# Jerry_microMouse.net
KiCad netlist of a schematic drawn in EAGLE
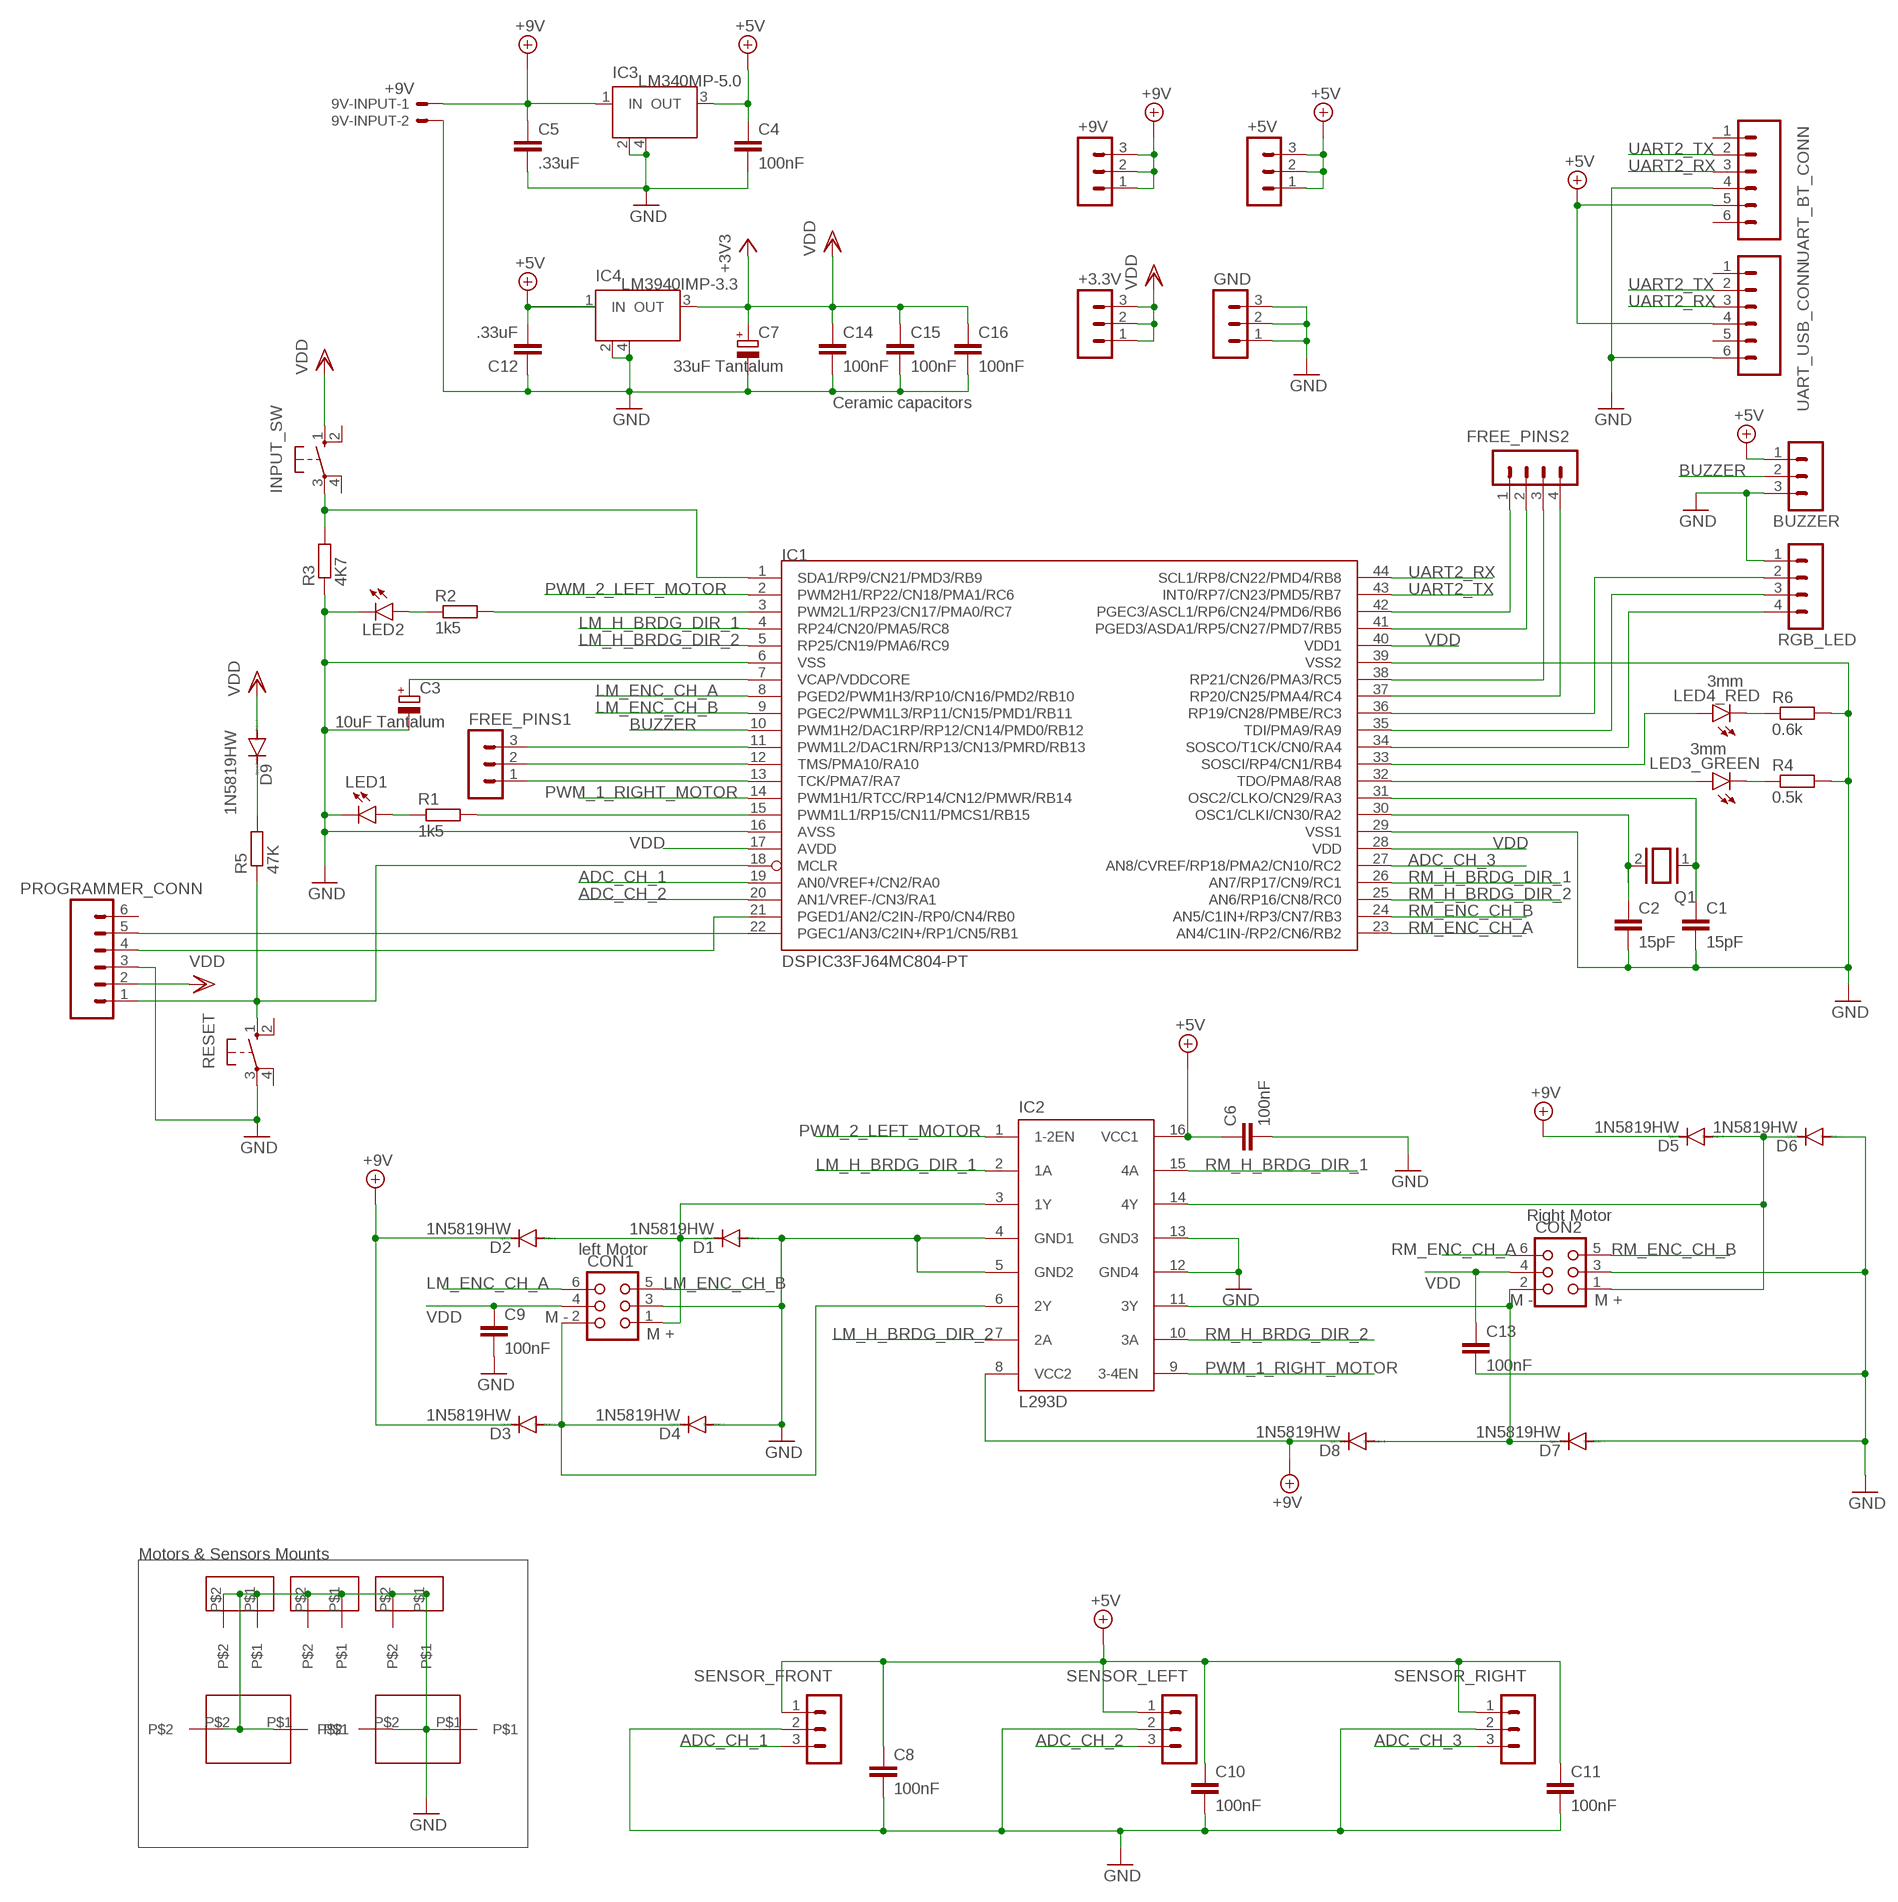
[diagram p0: schematic, sheet 1]

(export (version "E")
  (design (tool "Eeschema 10.0.6"))
  (components
    (comp (ref "+3.3V")
      (value "MA03-1")
      (footprint "eagle-import:MA03-1")
      (libsource (lib "eagle-import") (part "MA03-1"))
    )
    (comp (ref "+5V")
      (value "MA03-1")
      (footprint "eagle-import:MA03-1")
      (libsource (lib "eagle-import") (part "MA03-1"))
    )
    (comp (ref "+9V")
      (value "MA03-1")
      (footprint "eagle-import:MA03-1")
      (libsource (lib "eagle-import") (part "MA03-1"))
    )
    (comp (ref "9V-INPUT")
      (value "+9V")
      (footprint "eagle-import:22-23-2021")
      (fields (field (name "MF") "MOLEX") (field (name "MPN") "22-23-2021"))
      (libsource (lib "eagle-import") (part "22-23-2021"))
    )
    (comp (ref "BUZZER")
      (value "MA03-1")
      (footprint "eagle-import:MA03-1")
      (libsource (lib "eagle-import") (part "MA03-1"))
    )
    (comp (ref "C1")
      (value "15pF")
      (footprint "eagle-import:C0805")
      (libsource (lib "eagle-import") (part "C-EUC0805"))
    )
    (comp (ref "C2")
      (value "15pF")
      (footprint "eagle-import:C0805")
      (libsource (lib "eagle-import") (part "C-EUC0805"))
    )
    (comp (ref "C3")
      (value "10uF Tantalum")
      (footprint "eagle-import:CT3216")
      (libsource (lib "eagle-import") (part "CPOL-EUCT3216"))
    )
    (comp (ref "C4")
      (value "100nF")
      (footprint "eagle-import:C0805")
      (libsource (lib "eagle-import") (part "C-EUC0805"))
    )
    (comp (ref "C5")
      (value ".33uF")
      (footprint "eagle-import:C0805")
      (libsource (lib "eagle-import") (part "C-EUC0805"))
    )
    (comp (ref "C6")
      (value "100nF")
      (footprint "eagle-import:C0805")
      (libsource (lib "eagle-import") (part "C-EUC0805"))
    )
    (comp (ref "C7")
      (value "33uF Tantalum")
      (footprint "eagle-import:CT7343")
      (libsource (lib "eagle-import") (part "CPOL-EUCT7343"))
    )
    (comp (ref "C8")
      (value "100nF")
      (footprint "eagle-import:C0805")
      (libsource (lib "eagle-import") (part "C-EUC0805"))
    )
    (comp (ref "C9")
      (value "100nF")
      (footprint "eagle-import:C0805")
      (libsource (lib "eagle-import") (part "C-EUC0805"))
    )
    (comp (ref "C10")
      (value "100nF")
      (footprint "eagle-import:C0805")
      (libsource (lib "eagle-import") (part "C-EUC0805"))
    )
    (comp (ref "C11")
      (value "100nF")
      (footprint "eagle-import:C0805")
      (libsource (lib "eagle-import") (part "C-EUC0805"))
    )
    (comp (ref "C12")
      (value ".33uF")
      (footprint "eagle-import:C0805")
      (libsource (lib "eagle-import") (part "C-EUC0805"))
    )
    (comp (ref "C13")
      (value "100nF")
      (footprint "eagle-import:C0805")
      (libsource (lib "eagle-import") (part "C-EUC0805"))
    )
    (comp (ref "C14")
      (value "100nF")
      (footprint "eagle-import:C0805")
      (libsource (lib "eagle-import") (part "C-EUC0805"))
    )
    (comp (ref "C15")
      (value "100nF")
      (footprint "eagle-import:C0805")
      (libsource (lib "eagle-import") (part "C-EUC0805"))
    )
    (comp (ref "C16")
      (value "100nF")
      (footprint "eagle-import:C0805")
      (libsource (lib "eagle-import") (part "C-EUC0805"))
    )
    (comp (ref "CON1")
      (value "CON06L")
      (footprint "eagle-import:CON06L")
      (libsource (lib "eagle-import") (part "CON06L"))
    )
    (comp (ref "CON2")
      (value "CON06L")
      (footprint "eagle-import:CON06L")
      (libsource (lib "eagle-import") (part "CON06L"))
    )
    (comp (ref "D1")
      (value "1N5819HW")
      (footprint "eagle-import:SOD-123_MINI-SMA")
      (libsource (lib "eagle-import") (part "CGRM400-G1"))
    )
    (comp (ref "D2")
      (value "1N5819HW")
      (footprint "eagle-import:SOD-123_MINI-SMA")
      (libsource (lib "eagle-import") (part "CGRM400-G1"))
    )
    (comp (ref "D3")
      (value "1N5819HW")
      (footprint "eagle-import:SOD-123_MINI-SMA")
      (libsource (lib "eagle-import") (part "CGRM400-G1"))
    )
    (comp (ref "D4")
      (value "1N5819HW")
      (footprint "eagle-import:SOD-123_MINI-SMA")
      (libsource (lib "eagle-import") (part "CGRM400-G1"))
    )
    (comp (ref "D5")
      (value "1N5819HW")
      (footprint "eagle-import:SOD-123_MINI-SMA")
      (libsource (lib "eagle-import") (part "CGRM400-G1"))
    )
    (comp (ref "D6")
      (value "1N5819HW")
      (footprint "eagle-import:SOD-123_MINI-SMA")
      (libsource (lib "eagle-import") (part "CGRM400-G1"))
    )
    (comp (ref "D7")
      (value "1N5819HW")
      (footprint "eagle-import:SOD-123_MINI-SMA")
      (libsource (lib "eagle-import") (part "CGRM400-G1"))
    )
    (comp (ref "D8")
      (value "1N5819HW")
      (footprint "eagle-import:SOD-123_MINI-SMA")
      (libsource (lib "eagle-import") (part "CGRM400-G1"))
    )
    (comp (ref "D9")
      (value "1N5819HW")
      (footprint "eagle-import:SOD-123_MINI-SMA")
      (libsource (lib "eagle-import") (part "CGRM400-G1"))
    )
    (comp (ref "FREE_PINS1")
      (value "MA03-1")
      (footprint "eagle-import:MA03-1")
      (libsource (lib "eagle-import") (part "MA03-1"))
    )
    (comp (ref "FREE_PINS2")
      (value "MA04-1")
      (footprint "eagle-import:MA04-1")
      (libsource (lib "eagle-import") (part "MA04-1"))
    )
    (comp (ref "GND")
      (value "MA03-1")
      (footprint "eagle-import:MA03-1")
      (libsource (lib "eagle-import") (part "MA03-1"))
    )
    (comp (ref "IC1")
      (value "DSPIC33FJ64MC804-PT")
      (footprint "eagle-import:TQFP44")
      (libsource (lib "eagle-import") (part "DSPIC33FJ64MC804-PT"))
    )
    (comp (ref "IC2")
      (value "L293D")
      (footprint "eagle-import:DIL16")
      (libsource (lib "eagle-import") (part "L293D"))
    )
    (comp (ref "IC3")
      (value "LM340MP-5.0")
      (footprint "eagle-import:SOT223")
      (libsource (lib "eagle-import") (part "LM340S"))
    )
    (comp (ref "IC4")
      (value "LM3940IMP-3.3")
      (footprint "eagle-import:SOT223")
      (libsource (lib "eagle-import") (part "LM340S"))
    )
    (comp (ref "INPUT_SW")
      (value "10-XX")
      (footprint "eagle-import:B3F-10XX")
      (fields (field (name "MPN") "B3F-1000"))
      (libsource (lib "eagle-import") (part "10-XX"))
    )
    (comp (ref "LED1")
      (value "LED5MM")
      (footprint "eagle-import:LED5MM")
      (libsource (lib "eagle-import") (part "LED5MM"))
    )
    (comp (ref "LED2")
      (value "LED5MM")
      (footprint "eagle-import:LED5MM")
      (libsource (lib "eagle-import") (part "LED5MM"))
    )
    (comp (ref "LED3_GREEN")
      (value "3mm")
      (footprint "eagle-import:Q62902-B155")
      (libsource (lib "eagle-import") (part "LEDB155"))
    )
    (comp (ref "LED4_RED")
      (value "3mm")
      (footprint "eagle-import:Q62902-B155")
      (libsource (lib "eagle-import") (part "LEDB155"))
    )
    (comp (ref "PROGRAMMER_CONN")
      (value "M06")
      (footprint "eagle-import:06P")
      (libsource (lib "eagle-import") (part "M06"))
    )
    (comp (ref "Q1")
      (value "XTAL/S")
      (footprint "eagle-import:QS")
      (libsource (lib "eagle-import") (part "XTAL/S"))
    )
    (comp (ref "R1")
      (value "1k5")
      (footprint "eagle-import:R0805")
      (libsource (lib "eagle-import") (part "R-EU_R0805"))
    )
    (comp (ref "R2")
      (value "1k5")
      (footprint "eagle-import:R0805")
      (libsource (lib "eagle-import") (part "R-EU_R0805"))
    )
    (comp (ref "R3")
      (value "4K7")
      (footprint "eagle-import:R0805")
      (libsource (lib "eagle-import") (part "R-EU_R0805"))
    )
    (comp (ref "R4")
      (value "0.5k")
      (footprint "eagle-import:R0805")
      (libsource (lib "eagle-import") (part "R-EU_R0805"))
    )
    (comp (ref "R5")
      (value "47K")
      (footprint "eagle-import:R0805")
      (libsource (lib "eagle-import") (part "R-EU_R0805"))
    )
    (comp (ref "R6")
      (value "0.6k")
      (footprint "eagle-import:R0805")
      (libsource (lib "eagle-import") (part "R-EU_R0805"))
    )
    (comp (ref "RESET")
      (value "10-XX")
      (footprint "eagle-import:B3F-10XX")
      (fields (field (name "MPN") "B3F-1000"))
      (libsource (lib "eagle-import") (part "10-XX"))
    )
    (comp (ref "RGB_LED")
      (value "MA04-1")
      (footprint "eagle-import:MA04-1")
      (libsource (lib "eagle-import") (part "MA04-1"))
    )
    (comp (ref "SENSOR_FRONT")
      (value "MA03-1")
      (footprint "eagle-import:MA03-1")
      (libsource (lib "eagle-import") (part "MA03-1"))
    )
    (comp (ref "SENSOR_LEFT")
      (value "MA03-1")
      (footprint "eagle-import:MA03-1")
      (libsource (lib "eagle-import") (part "MA03-1"))
    )
    (comp (ref "SENSOR_RIGHT")
      (value "MA03-1")
      (footprint "eagle-import:MA03-1")
      (libsource (lib "eagle-import") (part "MA03-1"))
    )
    (comp (ref "SENS_MNT_F")
      (value "SENSOR_MOUNT_F")
      (footprint "eagle-import:SENSOR_MOUNT")
      (libsource (lib "eagle-import") (part "SENSOR_MOUNT"))
    )
    (comp (ref "SENS_MNT_L")
      (value "SENSOR_MOUNT_L")
      (footprint "eagle-import:SENSOR_MOUNT")
      (libsource (lib "eagle-import") (part "SENSOR_MOUNT"))
    )
    (comp (ref "SENS_MNT_R")
      (value "SENSOR_MOUNT_R")
      (footprint "eagle-import:SENSOR_MOUNT")
      (libsource (lib "eagle-import") (part "SENSOR_MOUNT"))
    )
    (comp (ref "U$1")
      (value "MOTOR_MOUNT")
      (footprint "eagle-import:MOTOR_MOUNT")
      (libsource (lib "eagle-import") (part "MOTOR_MOUNT"))
    )
    (comp (ref "U$2")
      (value "MOTOR_MOUNT")
      (footprint "eagle-import:MOTOR_MOUNT")
      (libsource (lib "eagle-import") (part "MOTOR_MOUNT"))
    )
    (comp (ref "UART_BT_CONN")
      (value "M06")
      (footprint "eagle-import:06P")
      (libsource (lib "eagle-import") (part "M06"))
    )
    (comp (ref "UART_USB_CONN")
      (value "M06")
      (footprint "eagle-import:06P")
      (libsource (lib "eagle-import") (part "M06"))
    )
  )
  (nets
    (net (code "1") (name "+3V3") (class "Default")
      (node (ref "+3.3V") (pin "1") (pinfunction "1_1") (pintype "passive"))
      (node (ref "+3.3V") (pin "2") (pinfunction "2_2") (pintype "passive"))
      (node (ref "+3.3V") (pin "3") (pinfunction "3_3") (pintype "passive"))
      (node (ref "C13") (pin "1") (pinfunction "1_1") (pintype "passive"))
      (node (ref "C14") (pin "1") (pinfunction "1_1") (pintype "passive"))
      (node (ref "C15") (pin "1") (pinfunction "1_1") (pintype "passive"))
      (node (ref "C16") (pin "1") (pinfunction "1_1") (pintype "passive"))
      (node (ref "C7") (pin "+") (pinfunction "+_+") (pintype "passive"))
      (node (ref "C9") (pin "1") (pinfunction "1_1") (pintype "passive"))
      (node (ref "CON1") (pin "4") (pinfunction "4_4") (pintype "passive"))
      (node (ref "CON2") (pin "4") (pinfunction "4_4") (pintype "passive"))
      (node (ref "D9") (pin "A") (pinfunction "A_A") (pintype "passive"))
      (node (ref "IC1") (pin "17") (pinfunction "AVDD_17") (pintype "power_in"))
      (node (ref "IC1") (pin "28") (pinfunction "VDD_28") (pintype "power_in"))
      (node (ref "IC1") (pin "40") (pinfunction "VDD1_40") (pintype "power_in"))
      (node (ref "IC4") (pin "3") (pinfunction "OUT_3") (pintype "passive"))
      (node (ref "INPUT_SW") (pin "1") (pinfunction "S_1") (pintype "passive"))
      (node (ref "PROGRAMMER_CONN") (pin "2") (pinfunction "2_2") (pintype "passive"))
    )
    (net (code "2") (name "+5V") (class "Default")
      (node (ref "+5V") (pin "1") (pinfunction "1_1") (pintype "passive"))
      (node (ref "+5V") (pin "2") (pinfunction "2_2") (pintype "passive"))
      (node (ref "+5V") (pin "3") (pinfunction "3_3") (pintype "passive"))
      (node (ref "BUZZER") (pin "1") (pinfunction "1_1") (pintype "passive"))
      (node (ref "C10") (pin "1") (pinfunction "1_1") (pintype "passive"))
      (node (ref "C11") (pin "1") (pinfunction "1_1") (pintype "passive"))
      (node (ref "C12") (pin "2") (pinfunction "2_2") (pintype "passive"))
      (node (ref "C4") (pin "1") (pinfunction "1_1") (pintype "passive"))
      (node (ref "C6") (pin "1") (pinfunction "1_1") (pintype "passive"))
      (node (ref "C8") (pin "1") (pinfunction "1_1") (pintype "passive"))
      (node (ref "IC2") (pin "16") (pinfunction "VCC1_16") (pintype "power_in"))
      (node (ref "IC3") (pin "3") (pinfunction "OUT_3") (pintype "passive"))
      (node (ref "IC4") (pin "1") (pinfunction "IN_1") (pintype "input"))
      (node (ref "SENSOR_FRONT") (pin "1") (pinfunction "1_1") (pintype "passive"))
      (node (ref "SENSOR_LEFT") (pin "1") (pinfunction "1_1") (pintype "passive"))
      (node (ref "SENSOR_RIGHT") (pin "1") (pinfunction "1_1") (pintype "passive"))
      (node (ref "UART_BT_CONN") (pin "5") (pinfunction "5_5") (pintype "passive"))
      (node (ref "UART_USB_CONN") (pin "4") (pinfunction "4_4") (pintype "passive"))
    )
    (net (code "3") (name "+9V") (class "Default")
      (node (ref "+9V") (pin "1") (pinfunction "1_1") (pintype "passive"))
      (node (ref "+9V") (pin "2") (pinfunction "2_2") (pintype "passive"))
      (node (ref "+9V") (pin "3") (pinfunction "3_3") (pintype "passive"))
      (node (ref "9V-INPUT") (pin "1") (pinfunction "S_1") (pintype "passive"))
      (node (ref "C5") (pin "1") (pinfunction "1_1") (pintype "passive"))
      (node (ref "D2") (pin "C") (pinfunction "C_C") (pintype "passive"))
      (node (ref "D3") (pin "C") (pinfunction "C_C") (pintype "passive"))
      (node (ref "D5") (pin "C") (pinfunction "C_C") (pintype "passive"))
      (node (ref "D8") (pin "C") (pinfunction "C_C") (pintype "passive"))
      (node (ref "IC2") (pin "8") (pinfunction "VCC2_8") (pintype "power_in"))
      (node (ref "IC3") (pin "1") (pinfunction "IN_1") (pintype "input"))
    )
    (net (code "4") (name "/ADC_CH_1") (class "Default")
      (node (ref "IC1") (pin "19") (pinfunction "AN0/VREF+/CN2/RA0_19") (pintype "bidirectional"))
      (node (ref "SENSOR_FRONT") (pin "3") (pinfunction "3_3") (pintype "passive"))
    )
    (net (code "5") (name "/ADC_CH_2") (class "Default")
      (node (ref "IC1") (pin "20") (pinfunction "AN1/VREF-/CN3/RA1_20") (pintype "bidirectional"))
      (node (ref "SENSOR_LEFT") (pin "3") (pinfunction "3_3") (pintype "passive"))
    )
    (net (code "6") (name "/ADC_CH_3") (class "Default")
      (node (ref "IC1") (pin "27") (pinfunction "AN8/CVREF/RP18/PMA2/CN10/RC2_27") (pintype "bidirectional"))
      (node (ref "SENSOR_RIGHT") (pin "3") (pinfunction "3_3") (pintype "passive"))
    )
    (net (code "7") (name "/BUZZER") (class "Default")
      (node (ref "BUZZER") (pin "2") (pinfunction "2_2") (pintype "passive"))
      (node (ref "IC1") (pin "10") (pinfunction "PWM1H2/DAC1RP/RP12/CN14/PMD0/RB12_10") (pintype "bidirectional"))
    )
    (net (code "8") (name "/LM_ENC_CH_A") (class "Default")
      (node (ref "CON1") (pin "6") (pinfunction "6_6") (pintype "passive"))
      (node (ref "IC1") (pin "8") (pinfunction "PGED2/PWM1H3/RP10/CN16/PMD2/RB10_8") (pintype "bidirectional"))
    )
    (net (code "9") (name "/LM_ENC_CH_B") (class "Default")
      (node (ref "CON1") (pin "5") (pinfunction "5_5") (pintype "passive"))
      (node (ref "IC1") (pin "9") (pinfunction "PGEC2/PWM1L3/RP11/CN15/PMD1/RB11_9") (pintype "bidirectional"))
    )
    (net (code "10") (name "/LM_H_BRDG_DIR_1") (class "Default")
      (node (ref "IC1") (pin "4") (pinfunction "RP24/CN20/PMA5/RC8_4") (pintype "bidirectional"))
      (node (ref "IC2") (pin "2") (pinfunction "1A_2") (pintype "input"))
    )
    (net (code "11") (name "/LM_H_BRDG_DIR_2") (class "Default")
      (node (ref "IC1") (pin "5") (pinfunction "RP25/CN19/PMA6/RC9_5") (pintype "bidirectional"))
      (node (ref "IC2") (pin "7") (pinfunction "2A_7") (pintype "input"))
    )
    (net (code "12") (name "/PWM_1_RIGHT_MOTOR") (class "Default")
      (node (ref "IC1") (pin "14") (pinfunction "PWM1H1/RTCC/RP14/CN12/PMWR/RB14_14") (pintype "bidirectional"))
      (node (ref "IC2") (pin "9") (pinfunction "3-4EN_9") (pintype "input"))
    )
    (net (code "13") (name "/PWM_2_LEFT_MOTOR") (class "Default")
      (node (ref "IC1") (pin "2") (pinfunction "PWM2H1/RP22/CN18/PMA1/RC6_2") (pintype "bidirectional"))
      (node (ref "IC2") (pin "1") (pinfunction "1-2EN_1") (pintype "input"))
    )
    (net (code "14") (name "/RM_ENC_CH_A") (class "Default")
      (node (ref "CON2") (pin "6") (pinfunction "6_6") (pintype "passive"))
      (node (ref "IC1") (pin "23") (pinfunction "AN4/C1IN-/RP2/CN6/RB2_23") (pintype "bidirectional"))
    )
    (net (code "15") (name "/RM_ENC_CH_B") (class "Default")
      (node (ref "CON2") (pin "5") (pinfunction "5_5") (pintype "passive"))
      (node (ref "IC1") (pin "24") (pinfunction "AN5/C1IN+/RP3/CN7/RB3_24") (pintype "bidirectional"))
    )
    (net (code "16") (name "/RM_H_BRDG_DIR_1") (class "Default")
      (node (ref "IC1") (pin "26") (pinfunction "AN7/RP17/CN9/RC1_26") (pintype "bidirectional"))
      (node (ref "IC2") (pin "15") (pinfunction "4A_15") (pintype "input"))
    )
    (net (code "17") (name "/RM_H_BRDG_DIR_2") (class "Default")
      (node (ref "IC1") (pin "25") (pinfunction "AN6/RP16/CN8/RC0_25") (pintype "bidirectional"))
      (node (ref "IC2") (pin "10") (pinfunction "3A_10") (pintype "input"))
    )
    (net (code "18") (name "/UART2_RX") (class "Default")
      (node (ref "IC1") (pin "44") (pinfunction "SCL1/RP8/CN22/PMD4/RB8_44") (pintype "bidirectional"))
      (node (ref "UART_BT_CONN") (pin "3") (pinfunction "3_3") (pintype "passive"))
      (node (ref "UART_USB_CONN") (pin "3") (pinfunction "3_3") (pintype "passive"))
    )
    (net (code "19") (name "/UART2_TX") (class "Default")
      (node (ref "IC1") (pin "43") (pinfunction "INT0/RP7/CN23/PMD5/RB7_43") (pintype "bidirectional"))
      (node (ref "UART_BT_CONN") (pin "2") (pinfunction "2_2") (pintype "passive"))
      (node (ref "UART_USB_CONN") (pin "2") (pinfunction "2_2") (pintype "passive"))
    )
    (net (code "20") (name "GND") (class "Default")
      (node (ref "9V-INPUT") (pin "2") (pinfunction "S_2") (pintype "passive"))
      (node (ref "BUZZER") (pin "3") (pinfunction "3_3") (pintype "passive"))
      (node (ref "C1") (pin "2") (pinfunction "2_2") (pintype "passive"))
      (node (ref "C10") (pin "2") (pinfunction "2_2") (pintype "passive"))
      (node (ref "C11") (pin "2") (pinfunction "2_2") (pintype "passive"))
      (node (ref "C12") (pin "1") (pinfunction "1_1") (pintype "passive"))
      (node (ref "C13") (pin "2") (pinfunction "2_2") (pintype "passive"))
      (node (ref "C14") (pin "2") (pinfunction "2_2") (pintype "passive"))
      (node (ref "C15") (pin "2") (pinfunction "2_2") (pintype "passive"))
      (node (ref "C16") (pin "2") (pinfunction "2_2") (pintype "passive"))
      (node (ref "C2") (pin "2") (pinfunction "2_2") (pintype "passive"))
      (node (ref "C3") (pin "-") (pinfunction "-_-") (pintype "passive"))
      (node (ref "C4") (pin "2") (pinfunction "2_2") (pintype "passive"))
      (node (ref "C5") (pin "2") (pinfunction "2_2") (pintype "passive"))
      (node (ref "C6") (pin "2") (pinfunction "2_2") (pintype "passive"))
      (node (ref "C7") (pin "-") (pinfunction "-_-") (pintype "passive"))
      (node (ref "C8") (pin "2") (pinfunction "2_2") (pintype "passive"))
      (node (ref "C9") (pin "2") (pinfunction "2_2") (pintype "passive"))
      (node (ref "CON1") (pin "3") (pinfunction "3_3") (pintype "passive"))
      (node (ref "CON2") (pin "3") (pinfunction "3_3") (pintype "passive"))
      (node (ref "D1") (pin "A") (pinfunction "A_A") (pintype "passive"))
      (node (ref "D4") (pin "A") (pinfunction "A_A") (pintype "passive"))
      (node (ref "D6") (pin "A") (pinfunction "A_A") (pintype "passive"))
      (node (ref "D7") (pin "A") (pinfunction "A_A") (pintype "passive"))
      (node (ref "GND") (pin "1") (pinfunction "1_1") (pintype "passive"))
      (node (ref "GND") (pin "2") (pinfunction "2_2") (pintype "passive"))
      (node (ref "GND") (pin "3") (pinfunction "3_3") (pintype "passive"))
      (node (ref "IC1") (pin "16") (pinfunction "AVSS_16") (pintype "power_in"))
      (node (ref "IC1") (pin "29") (pinfunction "VSS1_29") (pintype "power_in"))
      (node (ref "IC1") (pin "39") (pinfunction "VSS2_39") (pintype "power_in"))
      (node (ref "IC1") (pin "6") (pinfunction "VSS_6") (pintype "power_in"))
      (node (ref "IC2") (pin "12") (pinfunction "GND4_12") (pintype "power_in"))
      (node (ref "IC2") (pin "13") (pinfunction "GND3_13") (pintype "power_in"))
      (node (ref "IC2") (pin "4") (pinfunction "GND1_4") (pintype "power_in"))
      (node (ref "IC2") (pin "5") (pinfunction "GND2_5") (pintype "power_in"))
      (node (ref "IC3") (pin "2") (pinfunction "GND_2") (pintype "power_in"))
      (node (ref "IC3") (pin "4") (pinfunction "GND_4") (pintype "power_in"))
      (node (ref "IC4") (pin "2") (pinfunction "GND_2") (pintype "power_in"))
      (node (ref "IC4") (pin "4") (pinfunction "GND_4") (pintype "power_in"))
      (node (ref "LED1") (pin "K") (pinfunction "C_K") (pintype "passive"))
      (node (ref "LED2") (pin "K") (pinfunction "C_K") (pintype "passive"))
      (node (ref "PROGRAMMER_CONN") (pin "3") (pinfunction "3_3") (pintype "passive"))
      (node (ref "R3") (pin "1") (pinfunction "1_1") (pintype "passive"))
      (node (ref "R4") (pin "2") (pinfunction "2_2") (pintype "passive"))
      (node (ref "R6") (pin "2") (pinfunction "2_2") (pintype "passive"))
      (node (ref "RESET") (pin "3") (pinfunction "P_3") (pintype "passive"))
      (node (ref "RGB_LED") (pin "1") (pinfunction "1_1") (pintype "passive"))
      (node (ref "SENSOR_FRONT") (pin "2") (pinfunction "2_2") (pintype "passive"))
      (node (ref "SENSOR_LEFT") (pin "2") (pinfunction "2_2") (pintype "passive"))
      (node (ref "SENSOR_RIGHT") (pin "2") (pinfunction "2_2") (pintype "passive"))
      (node (ref "SENS_MNT_F") (pin "P$1") (pinfunction "P$1_P$1") (pintype "bidirectional"))
      (node (ref "SENS_MNT_F") (pin "P$2") (pinfunction "P$2_P$2") (pintype "bidirectional"))
      (node (ref "SENS_MNT_L") (pin "P$1") (pinfunction "P$1_P$1") (pintype "bidirectional"))
      (node (ref "SENS_MNT_L") (pin "P$2") (pinfunction "P$2_P$2") (pintype "bidirectional"))
      (node (ref "SENS_MNT_R") (pin "P$1") (pinfunction "P$1_P$1") (pintype "bidirectional"))
      (node (ref "SENS_MNT_R") (pin "P$2") (pinfunction "P$2_P$2") (pintype "bidirectional"))
      (node (ref "U$1") (pin "P$1") (pinfunction "P$1_P$1") (pintype "bidirectional"))
      (node (ref "U$1") (pin "P$2") (pinfunction "P$2_P$2") (pintype "bidirectional"))
      (node (ref "U$2") (pin "P$1") (pinfunction "P$1_P$1") (pintype "bidirectional"))
      (node (ref "U$2") (pin "P$2") (pinfunction "P$2_P$2") (pintype "bidirectional"))
      (node (ref "UART_BT_CONN") (pin "4") (pinfunction "4_4") (pintype "passive"))
      (node (ref "UART_USB_CONN") (pin "6") (pinfunction "6_6") (pintype "passive"))
    )
    (net (code "21") (name "Net-(D9-PadC)") (class "Default")
      (node (ref "D9") (pin "C") (pinfunction "C_C") (pintype "passive"))
      (node (ref "R5") (pin "2") (pinfunction "2_2") (pintype "passive"))
    )
    (net (code "22") (name "Net-(IC1-MCLR)") (class "Default")
      (node (ref "IC1") (pin "18") (pinfunction "MCLR_18") (pintype "input"))
      (node (ref "PROGRAMMER_CONN") (pin "1") (pinfunction "1_1") (pintype "passive"))
      (node (ref "R5") (pin "1") (pinfunction "1_1") (pintype "passive"))
      (node (ref "RESET") (pin "1") (pinfunction "S_1") (pintype "passive"))
    )
    (net (code "23") (name "Net-(IC1-OSC1{slash}CLKI{slash}CN30{slash}RA2)") (class "Default")
      (node (ref "C2") (pin "1") (pinfunction "1_1") (pintype "passive"))
      (node (ref "IC1") (pin "30") (pinfunction "OSC1/CLKI/CN30/RA2_30") (pintype "bidirectional"))
      (node (ref "Q1") (pin "2") (pinfunction "2_2") (pintype "passive"))
    )
    (net (code "24") (name "Net-(IC1-OSC2{slash}CLKO{slash}CN29{slash}RA3)") (class "Default")
      (node (ref "C1") (pin "1") (pinfunction "1_1") (pintype "passive"))
      (node (ref "IC1") (pin "31") (pinfunction "OSC2/CLKO/CN29/RA3_31") (pintype "bidirectional"))
      (node (ref "Q1") (pin "1") (pinfunction "1_1") (pintype "passive"))
    )
    (net (code "25") (name "Net-(IC1-PGEC1{slash}AN3{slash}C2IN+{slash}RP1{slash}CN5{slash}RB1)") (class "Default")
      (node (ref "IC1") (pin "22") (pinfunction "PGEC1/AN3/C2IN+/RP1/CN5/RB1_22") (pintype "bidirectional"))
      (node (ref "PROGRAMMER_CONN") (pin "5") (pinfunction "5_5") (pintype "passive"))
    )
    (net (code "26") (name "Net-(IC1-PGEC3{slash}ASCL1{slash}RP6{slash}CN24{slash}PMD6{slash}RB6)") (class "Default")
      (node (ref "FREE_PINS2") (pin "1") (pinfunction "1_1") (pintype "passive"))
      (node (ref "IC1") (pin "42") (pinfunction "PGEC3/ASCL1/RP6/CN24/PMD6/RB6_42") (pintype "bidirectional"))
    )
    (net (code "27") (name "Net-(IC1-PGED1{slash}AN2{slash}C2IN-{slash}RP0{slash}CN4{slash}RB0)") (class "Default")
      (node (ref "IC1") (pin "21") (pinfunction "PGED1/AN2/C2IN-/RP0/CN4/RB0_21") (pintype "bidirectional"))
      (node (ref "PROGRAMMER_CONN") (pin "4") (pinfunction "4_4") (pintype "passive"))
    )
    (net (code "28") (name "Net-(IC1-PGED3{slash}ASDA1{slash}RP5{slash}CN27{slash}PMD7{slash}RB5)") (class "Default")
      (node (ref "FREE_PINS2") (pin "2") (pinfunction "2_2") (pintype "passive"))
      (node (ref "IC1") (pin "41") (pinfunction "PGED3/ASDA1/RP5/CN27/PMD7/RB5_41") (pintype "bidirectional"))
    )
    (net (code "29") (name "Net-(IC1-PWM1L1{slash}RP15{slash}CN11{slash}PMCS1{slash}RB15)") (class "Default")
      (node (ref "IC1") (pin "15") (pinfunction "PWM1L1/RP15/CN11/PMCS1/RB15_15") (pintype "bidirectional"))
      (node (ref "R1") (pin "2") (pinfunction "2_2") (pintype "passive"))
    )
    (net (code "30") (name "Net-(IC1-PWM1L2{slash}DAC1RN{slash}RP13{slash}CN13{slash}PMRD{slash}RB13)") (class "Default")
      (node (ref "FREE_PINS1") (pin "3") (pinfunction "3_3") (pintype "passive"))
      (node (ref "IC1") (pin "11") (pinfunction "PWM1L2/DAC1RN/RP13/CN13/PMRD/RB13_11") (pintype "bidirectional"))
    )
    (net (code "31") (name "Net-(IC1-PWM2L1{slash}RP23{slash}CN17{slash}PMA0{slash}RC7)") (class "Default")
      (node (ref "IC1") (pin "3") (pinfunction "PWM2L1/RP23/CN17/PMA0/RC7_3") (pintype "bidirectional"))
      (node (ref "R2") (pin "2") (pinfunction "2_2") (pintype "passive"))
    )
    (net (code "32") (name "Net-(IC1-RP19{slash}CN28{slash}PMBE{slash}RC3)") (class "Default")
      (node (ref "IC1") (pin "36") (pinfunction "RP19/CN28/PMBE/RC3_36") (pintype "bidirectional"))
      (node (ref "RGB_LED") (pin "2") (pinfunction "2_2") (pintype "passive"))
    )
    (net (code "33") (name "Net-(IC1-RP20{slash}CN25{slash}PMA4{slash}RC4)") (class "Default")
      (node (ref "FREE_PINS2") (pin "4") (pinfunction "4_4") (pintype "passive"))
      (node (ref "IC1") (pin "37") (pinfunction "RP20/CN25/PMA4/RC4_37") (pintype "bidirectional"))
    )
    (net (code "34") (name "Net-(IC1-RP21{slash}CN26{slash}PMA3{slash}RC5)") (class "Default")
      (node (ref "FREE_PINS2") (pin "3") (pinfunction "3_3") (pintype "passive"))
      (node (ref "IC1") (pin "38") (pinfunction "RP21/CN26/PMA3/RC5_38") (pintype "bidirectional"))
    )
    (net (code "35") (name "Net-(IC1-SDA1{slash}RP9{slash}CN21{slash}PMD3{slash}RB9)") (class "Default")
      (node (ref "IC1") (pin "1") (pinfunction "SDA1/RP9/CN21/PMD3/RB9_1") (pintype "bidirectional"))
      (node (ref "INPUT_SW") (pin "3") (pinfunction "P_3") (pintype "passive"))
      (node (ref "R3") (pin "2") (pinfunction "2_2") (pintype "passive"))
    )
    (net (code "36") (name "Net-(IC1-SOSCI{slash}RP4{slash}CN1{slash}RB4)") (class "Default")
      (node (ref "IC1") (pin "33") (pinfunction "SOSCI/RP4/CN1/RB4_33") (pintype "bidirectional"))
      (node (ref "LED4_RED") (pin "A") (pinfunction "A_A") (pintype "passive"))
    )
    (net (code "37") (name "Net-(IC1-SOSCO{slash}T1CK{slash}CN0{slash}RA4)") (class "Default")
      (node (ref "IC1") (pin "34") (pinfunction "SOSCO/T1CK/CN0/RA4_34") (pintype "bidirectional"))
      (node (ref "RGB_LED") (pin "4") (pinfunction "4_4") (pintype "passive"))
    )
    (net (code "38") (name "Net-(IC1-TCK{slash}PMA7{slash}RA7)") (class "Default")
      (node (ref "FREE_PINS1") (pin "1") (pinfunction "1_1") (pintype "passive"))
      (node (ref "IC1") (pin "13") (pinfunction "TCK/PMA7/RA7_13") (pintype "bidirectional"))
    )
    (net (code "39") (name "Net-(IC1-TDI{slash}PMA9{slash}RA9)") (class "Default")
      (node (ref "IC1") (pin "35") (pinfunction "TDI/PMA9/RA9_35") (pintype "bidirectional"))
      (node (ref "RGB_LED") (pin "3") (pinfunction "3_3") (pintype "passive"))
    )
    (net (code "40") (name "Net-(IC1-TDO{slash}PMA8{slash}RA8)") (class "Default")
      (node (ref "IC1") (pin "32") (pinfunction "TDO/PMA8/RA8_32") (pintype "bidirectional"))
      (node (ref "LED3_GREEN") (pin "A") (pinfunction "A_A") (pintype "passive"))
    )
    (net (code "41") (name "Net-(IC1-TMS{slash}PMA10{slash}RA10)") (class "Default")
      (node (ref "FREE_PINS1") (pin "2") (pinfunction "2_2") (pintype "passive"))
      (node (ref "IC1") (pin "12") (pinfunction "TMS/PMA10/RA10_12") (pintype "bidirectional"))
    )
    (net (code "42") (name "Net-(IC1-VCAP{slash}VDDCORE)") (class "Default")
      (node (ref "C3") (pin "+") (pinfunction "+_+") (pintype "passive"))
      (node (ref "IC1") (pin "7") (pinfunction "VCAP/VDDCORE_7") (pintype "power_in"))
    )
    (net (code "43") (name "Net-(IC2-1Y)") (class "Default")
      (node (ref "CON1") (pin "1") (pinfunction "1_1") (pintype "passive"))
      (node (ref "D1") (pin "C") (pinfunction "C_C") (pintype "passive"))
      (node (ref "D2") (pin "A") (pinfunction "A_A") (pintype "passive"))
      (node (ref "IC2") (pin "3") (pinfunction "1Y_3") (pintype "output"))
    )
    (net (code "44") (name "Net-(IC2-2Y)") (class "Default")
      (node (ref "CON1") (pin "2") (pinfunction "2_2") (pintype "passive"))
      (node (ref "D3") (pin "A") (pinfunction "A_A") (pintype "passive"))
      (node (ref "D4") (pin "C") (pinfunction "C_C") (pintype "passive"))
      (node (ref "IC2") (pin "6") (pinfunction "2Y_6") (pintype "output"))
    )
    (net (code "45") (name "Net-(IC2-3Y)") (class "Default")
      (node (ref "CON2") (pin "2") (pinfunction "2_2") (pintype "passive"))
      (node (ref "D7") (pin "C") (pinfunction "C_C") (pintype "passive"))
      (node (ref "D8") (pin "A") (pinfunction "A_A") (pintype "passive"))
      (node (ref "IC2") (pin "11") (pinfunction "3Y_11") (pintype "output"))
    )
    (net (code "46") (name "Net-(IC2-4Y)") (class "Default")
      (node (ref "CON2") (pin "1") (pinfunction "1_1") (pintype "passive"))
      (node (ref "D5") (pin "A") (pinfunction "A_A") (pintype "passive"))
      (node (ref "D6") (pin "C") (pinfunction "C_C") (pintype "passive"))
      (node (ref "IC2") (pin "14") (pinfunction "4Y_14") (pintype "output"))
    )
    (net (code "47") (name "Net-(LED1-PadA)") (class "Default")
      (node (ref "LED1") (pin "A") (pinfunction "A_A") (pintype "passive"))
      (node (ref "R1") (pin "1") (pinfunction "1_1") (pintype "passive"))
    )
    (net (code "48") (name "Net-(LED2-PadA)") (class "Default")
      (node (ref "LED2") (pin "A") (pinfunction "A_A") (pintype "passive"))
      (node (ref "R2") (pin "1") (pinfunction "1_1") (pintype "passive"))
    )
    (net (code "49") (name "Net-(LED3_GREEN-C)") (class "Default")
      (node (ref "LED3_GREEN") (pin "K") (pinfunction "C_K") (pintype "passive"))
      (node (ref "R4") (pin "1") (pinfunction "1_1") (pintype "passive"))
    )
    (net (code "50") (name "Net-(LED4_RED-C)") (class "Default")
      (node (ref "LED4_RED") (pin "K") (pinfunction "C_K") (pintype "passive"))
      (node (ref "R6") (pin "1") (pinfunction "1_1") (pintype "passive"))
    )
    (net (code "51") (name "unconnected-(INPUT_SW-P1-Pad4)") (class "Default")
      (node (ref "INPUT_SW") (pin "4") (pinfunction "P1_4") (pintype "passive"))
    )
    (net (code "52") (name "unconnected-(INPUT_SW-S1-Pad2)") (class "Default")
      (node (ref "INPUT_SW") (pin "2") (pinfunction "S1_2") (pintype "passive"))
    )
    (net (code "53") (name "unconnected-(PROGRAMMER_CONN-Pad6)") (class "Default")
      (node (ref "PROGRAMMER_CONN") (pin "6") (pinfunction "6_6") (pintype "passive"))
    )
    (net (code "54") (name "unconnected-(RESET-P1-Pad4)") (class "Default")
      (node (ref "RESET") (pin "4") (pinfunction "P1_4") (pintype "passive"))
    )
    (net (code "55") (name "unconnected-(RESET-S1-Pad2)") (class "Default")
      (node (ref "RESET") (pin "2") (pinfunction "S1_2") (pintype "passive"))
    )
    (net (code "56") (name "unconnected-(UART_BT_CONN-Pad1)") (class "Default")
      (node (ref "UART_BT_CONN") (pin "1") (pinfunction "1_1") (pintype "passive"))
    )
    (net (code "57") (name "unconnected-(UART_BT_CONN-Pad6)") (class "Default")
      (node (ref "UART_BT_CONN") (pin "6") (pinfunction "6_6") (pintype "passive"))
    )
    (net (code "58") (name "unconnected-(UART_USB_CONN-Pad1)") (class "Default")
      (node (ref "UART_USB_CONN") (pin "1") (pinfunction "1_1") (pintype "passive"))
    )
    (net (code "59") (name "unconnected-(UART_USB_CONN-Pad5)") (class "Default")
      (node (ref "UART_USB_CONN") (pin "5") (pinfunction "5_5") (pintype "passive"))
    )
  )
)
